# ztsh_autoguide.net
KiCad netlist of a schematic drawn in EAGLE
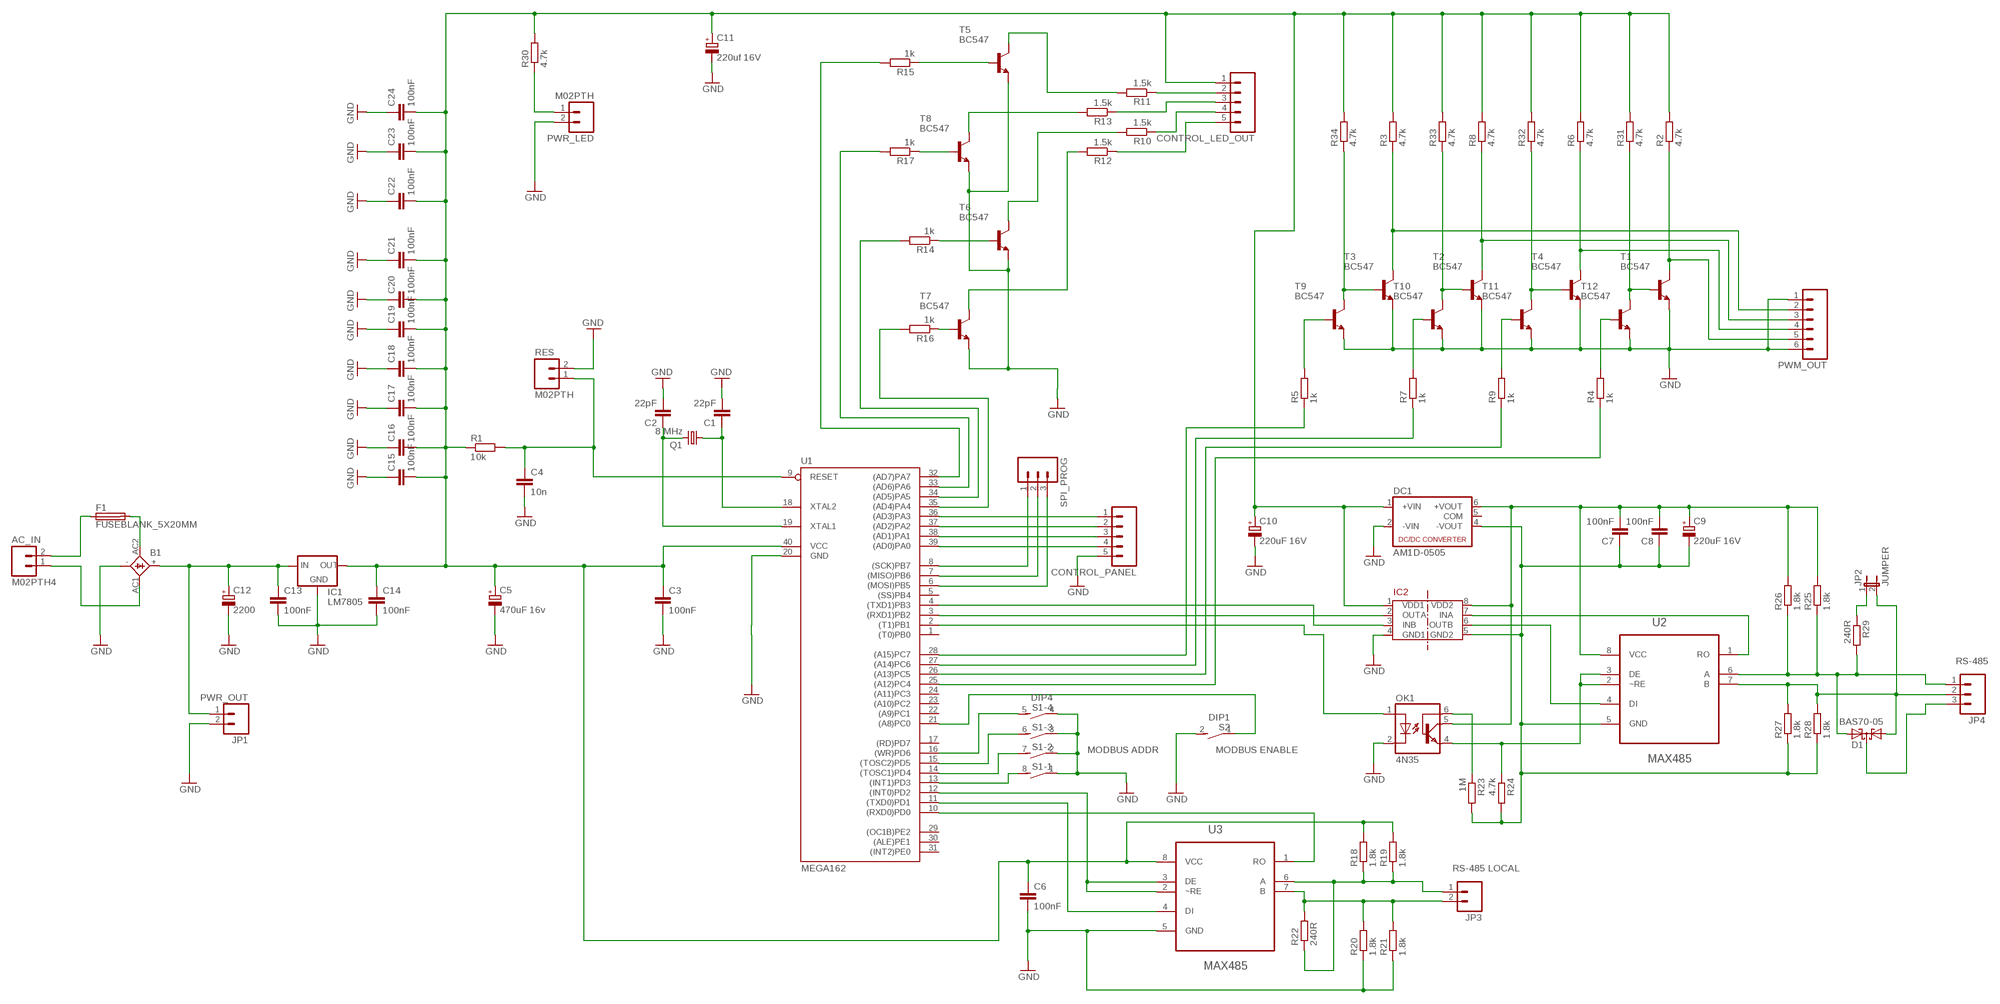
[diagram p0: schematic, sheet 1]

(export (version "E")
  (design (tool "Eeschema 10.0.6"))
  (components
    (comp (ref "AC_IN")
      (value "M02PTH4")
      (footprint "eagle-import:1X02_XTRA_BIG")
      (libsource (lib "eagle-import") (part "M02PTH4"))
    )
    (comp (ref "B1")
      (value "KBL")
      (footprint "eagle-import:KBL")
      (libsource (lib "eagle-import") (part "KBL"))
    )
    (comp (ref "C1")
      (value "22pF")
      (footprint "eagle-import:C025-024X044")
      (libsource (lib "eagle-import") (part "C-EU025-024X044"))
    )
    (comp (ref "C2")
      (value "22pF")
      (footprint "eagle-import:C025-024X044")
      (libsource (lib "eagle-import") (part "C-EU025-024X044"))
    )
    (comp (ref "C3")
      (value "100nF")
      (footprint "eagle-import:C0805")
      (libsource (lib "eagle-import") (part "C-EUC0805"))
    )
    (comp (ref "C4")
      (value "10n")
      (footprint "eagle-import:C0805")
      (libsource (lib "eagle-import") (part "C-EUC0805"))
    )
    (comp (ref "C5")
      (value "470uF 16v")
      (footprint "eagle-import:E2-5")
      (libsource (lib "eagle-import") (part "CPOL-EUE2-5"))
    )
    (comp (ref "C6")
      (value "100nF")
      (footprint "eagle-import:C0805")
      (libsource (lib "eagle-import") (part "C-EUC0805"))
    )
    (comp (ref "C7")
      (value "100nF")
      (footprint "eagle-import:C0805")
      (libsource (lib "eagle-import") (part "C-EUC0805"))
    )
    (comp (ref "C8")
      (value "100nF")
      (footprint "eagle-import:C0805")
      (libsource (lib "eagle-import") (part "C-EUC0805"))
    )
    (comp (ref "C9")
      (value "220uF 16V")
      (footprint "eagle-import:E2-5")
      (libsource (lib "eagle-import") (part "CPOL-EUE2-5"))
    )
    (comp (ref "C10")
      (value "220uF 16V")
      (footprint "eagle-import:E2-5")
      (libsource (lib "eagle-import") (part "CPOL-EUE2-5"))
    )
    (comp (ref "C11")
      (value "220uf 16V")
      (footprint "eagle-import:E2-5")
      (libsource (lib "eagle-import") (part "CPOL-EUE2-5"))
    )
    (comp (ref "C12")
      (value "2200")
      (footprint "eagle-import:E3,5-10")
      (libsource (lib "eagle-import") (part "resistor_CPOL-EUE3.5-10"))
    )
    (comp (ref "C13")
      (value "100nF")
      (footprint "eagle-import:C0805")
      (libsource (lib "eagle-import") (part "C-EUC0805"))
    )
    (comp (ref "C14")
      (value "100nF")
      (footprint "eagle-import:C0805")
      (libsource (lib "eagle-import") (part "C-EUC0805"))
    )
    (comp (ref "C15")
      (value "100nF")
      (footprint "eagle-import:C0805")
      (libsource (lib "eagle-import") (part "C-EUC0805"))
    )
    (comp (ref "C16")
      (value "100nF")
      (footprint "eagle-import:C0805")
      (libsource (lib "eagle-import") (part "C-EUC0805"))
    )
    (comp (ref "C17")
      (value "100nF")
      (footprint "eagle-import:C0805")
      (libsource (lib "eagle-import") (part "C-EUC0805"))
    )
    (comp (ref "C18")
      (value "100nF")
      (footprint "eagle-import:C0805")
      (libsource (lib "eagle-import") (part "C-EUC0805"))
    )
    (comp (ref "C19")
      (value "100nF")
      (footprint "eagle-import:C0805")
      (libsource (lib "eagle-import") (part "C-EUC0805"))
    )
    (comp (ref "C20")
      (value "100nF")
      (footprint "eagle-import:C0805")
      (libsource (lib "eagle-import") (part "C-EUC0805"))
    )
    (comp (ref "C21")
      (value "100nF")
      (footprint "eagle-import:C0805")
      (libsource (lib "eagle-import") (part "C-EUC0805"))
    )
    (comp (ref "C22")
      (value "100nF")
      (footprint "eagle-import:C0805")
      (libsource (lib "eagle-import") (part "C-EUC0805"))
    )
    (comp (ref "C23")
      (value "100nF")
      (footprint "eagle-import:C0805")
      (libsource (lib "eagle-import") (part "C-EUC0805"))
    )
    (comp (ref "C24")
      (value "100nF")
      (footprint "eagle-import:C0805")
      (libsource (lib "eagle-import") (part "C-EUC0805"))
    )
    (comp (ref "CONTROL_LED_OUT")
      (value "M05LOCK")
      (footprint "eagle-import:1X05_LOCK")
      (libsource (lib "eagle-import") (part "M05LOCK"))
    )
    (comp (ref "CONTROL_PANEL")
      (value "M05LOCK")
      (footprint "eagle-import:1X05_LOCK")
      (libsource (lib "eagle-import") (part "M05LOCK"))
    )
    (comp (ref "D1")
      (value "BAS70-05")
      (footprint "eagle-import:SOT23")
      (libsource (lib "eagle-import") (part "BAS70-05"))
    )
    (comp (ref "DC1")
      (value "AM1D-0505")
      (footprint "eagle-import:NMA")
      (fields (field (name "MF") "C & D TECHNOLOGIES, INC") (field (name "MPN") "NMA0515SC"))
      (libsource (lib "eagle-import") (part "NMA"))
    )
    (comp (ref "F1")
      (value "FUSEBLANK_5X20MM")
      (footprint "eagle-import:FUSE_HOLDER_5X20MM")
      (libsource (lib "eagle-import") (part "FUSEBLANK_5X20MM"))
    )
    (comp (ref "IC1")
      (value "LM7805")
      (footprint "eagle-import:TO-220-ALT")
      (libsource (lib "eagle-import") (part "V_REG_78XX-TO-220"))
    )
    (comp (ref "IC2")
      (value "ADUM1201")
      (footprint "eagle-import:SO8")
      (libsource (lib "eagle-import") (part "ADUM1201"))
    )
    (comp (ref "JP1")
      (value "PWR_OUT")
      (footprint "eagle-import:1X02_LOCK_LONGPADS")
      (libsource (lib "eagle-import") (part "M02LOCK_LONGPADS"))
    )
    (comp (ref "JP2")
      (value "JUMPER")
      (footprint "eagle-import:JP1")
      (libsource (lib "eagle-import") (part "JP1E"))
    )
    (comp (ref "JP3")
      (value "M02JST-PTH-VERT")
      (footprint "eagle-import:JST-2-PTH-VERT")
      (libsource (lib "eagle-import") (part "M02JST-PTH-VERT"))
    )
    (comp (ref "JP4")
      (value "M03JST-PTH-VERT")
      (footprint "eagle-import:JST-3-PTH-VERT")
      (libsource (lib "eagle-import") (part "M03JST-PTH-VERT"))
    )
    (comp (ref "OK1")
      (value "4N35")
      (footprint "eagle-import:DIL06")
      (fields (field (name "MF") "FAIRCHILD SEMICONDUCTOR"))
      (libsource (lib "eagle-import") (part "4N35"))
    )
    (comp (ref "PWM_OUT")
      (value "M06LOCK")
      (footprint "eagle-import:1X06_LOCK")
      (libsource (lib "eagle-import") (part "M06LOCK"))
    )
    (comp (ref "PWR_LED")
      (value "M02PTH")
      (footprint "eagle-import:1X02")
      (libsource (lib "eagle-import") (part "M02PTH"))
    )
    (comp (ref "Q1")
      (value "8 MHz")
      (footprint "eagle-import:HC18U-V")
      (libsource (lib "eagle-import") (part "CRYSTALHC18U-V"))
    )
    (comp (ref "R1")
      (value "10k")
      (footprint "eagle-import:0207_10")
      (libsource (lib "eagle-import") (part "R-EU_0207/10"))
    )
    (comp (ref "R2")
      (value "4.7k")
      (footprint "eagle-import:0204_7")
      (libsource (lib "eagle-import") (part "R-EU_0204/7"))
    )
    (comp (ref "R3")
      (value "4.7k")
      (footprint "eagle-import:0204_7")
      (libsource (lib "eagle-import") (part "R-EU_0204/7"))
    )
    (comp (ref "R4")
      (value "1k")
      (footprint "eagle-import:0204_7")
      (libsource (lib "eagle-import") (part "R-EU_0204/7"))
    )
    (comp (ref "R5")
      (value "1k")
      (footprint "eagle-import:0204_7")
      (libsource (lib "eagle-import") (part "R-EU_0204/7"))
    )
    (comp (ref "R6")
      (value "4.7k")
      (footprint "eagle-import:0204_7")
      (libsource (lib "eagle-import") (part "R-EU_0204/7"))
    )
    (comp (ref "R7")
      (value "1k")
      (footprint "eagle-import:0204_7")
      (libsource (lib "eagle-import") (part "R-EU_0204/7"))
    )
    (comp (ref "R8")
      (value "4.7k")
      (footprint "eagle-import:0204_7")
      (libsource (lib "eagle-import") (part "R-EU_0204/7"))
    )
    (comp (ref "R9")
      (value "1k")
      (footprint "eagle-import:0204_7")
      (libsource (lib "eagle-import") (part "R-EU_0204/7"))
    )
    (comp (ref "R10")
      (value "1.5k")
      (footprint "eagle-import:0204_7")
      (libsource (lib "eagle-import") (part "R-EU_0204/7"))
    )
    (comp (ref "R11")
      (value "1.5k")
      (footprint "eagle-import:0204_7")
      (libsource (lib "eagle-import") (part "R-EU_0204/7"))
    )
    (comp (ref "R12")
      (value "1.5k")
      (footprint "eagle-import:0204_7")
      (libsource (lib "eagle-import") (part "R-EU_0204/7"))
    )
    (comp (ref "R13")
      (value "1.5k")
      (footprint "eagle-import:0204_7")
      (libsource (lib "eagle-import") (part "R-EU_0204/7"))
    )
    (comp (ref "R14")
      (value "1k")
      (footprint "eagle-import:0204_7")
      (libsource (lib "eagle-import") (part "R-EU_0204/7"))
    )
    (comp (ref "R15")
      (value "1k")
      (footprint "eagle-import:0204_7")
      (libsource (lib "eagle-import") (part "R-EU_0204/7"))
    )
    (comp (ref "R16")
      (value "1k")
      (footprint "eagle-import:0204_7")
      (libsource (lib "eagle-import") (part "R-EU_0204/7"))
    )
    (comp (ref "R17")
      (value "1k")
      (footprint "eagle-import:0204_7")
      (libsource (lib "eagle-import") (part "R-EU_0204/7"))
    )
    (comp (ref "R18")
      (value "1.8k")
      (footprint "eagle-import:R0805")
      (libsource (lib "eagle-import") (part "R-EU_R0805"))
    )
    (comp (ref "R19")
      (value "1.8k")
      (footprint "eagle-import:R0805")
      (libsource (lib "eagle-import") (part "R-EU_R0805"))
    )
    (comp (ref "R20")
      (value "1.8k")
      (footprint "eagle-import:R0805")
      (libsource (lib "eagle-import") (part "R-EU_R0805"))
    )
    (comp (ref "R21")
      (value "1.8k")
      (footprint "eagle-import:R0805")
      (libsource (lib "eagle-import") (part "R-EU_R0805"))
    )
    (comp (ref "R22")
      (value "240R")
      (footprint "eagle-import:R0805")
      (libsource (lib "eagle-import") (part "R-EU_R0805"))
    )
    (comp (ref "R23")
      (value "1M")
      (footprint "eagle-import:0204_7")
      (libsource (lib "eagle-import") (part "R-EU_0204/7"))
    )
    (comp (ref "R24")
      (value "4.7k")
      (footprint "eagle-import:0204_7")
      (libsource (lib "eagle-import") (part "R-EU_0204/7"))
    )
    (comp (ref "R25")
      (value "1.8k")
      (footprint "eagle-import:R0805")
      (libsource (lib "eagle-import") (part "R-EU_R0805"))
    )
    (comp (ref "R26")
      (value "1.8k")
      (footprint "eagle-import:R0805")
      (libsource (lib "eagle-import") (part "R-EU_R0805"))
    )
    (comp (ref "R27")
      (value "1.8k")
      (footprint "eagle-import:R0805")
      (libsource (lib "eagle-import") (part "R-EU_R0805"))
    )
    (comp (ref "R28")
      (value "1.8k")
      (footprint "eagle-import:R0805")
      (libsource (lib "eagle-import") (part "R-EU_R0805"))
    )
    (comp (ref "R29")
      (value "240R")
      (footprint "eagle-import:R0805")
      (libsource (lib "eagle-import") (part "R-EU_R0805"))
    )
    (comp (ref "R30")
      (value "4.7k")
      (footprint "eagle-import:0207_10")
      (libsource (lib "eagle-import") (part "R-EU_0207/10"))
    )
    (comp (ref "R31")
      (value "4.7k")
      (footprint "eagle-import:0204_7")
      (libsource (lib "eagle-import") (part "R-EU_0204/7"))
    )
    (comp (ref "R32")
      (value "4.7k")
      (footprint "eagle-import:0204_7")
      (libsource (lib "eagle-import") (part "R-EU_0204/7"))
    )
    (comp (ref "R33")
      (value "4.7k")
      (footprint "eagle-import:0204_7")
      (libsource (lib "eagle-import") (part "R-EU_0204/7"))
    )
    (comp (ref "R34")
      (value "4.7k")
      (footprint "eagle-import:0204_7")
      (libsource (lib "eagle-import") (part "R-EU_0204/7"))
    )
    (comp (ref "RES")
      (value "M02PTH")
      (footprint "eagle-import:1X02")
      (libsource (lib "eagle-import") (part "M02PTH"))
    )
    (comp (ref "S1")
      (value "DIP4")
      (footprint "eagle-import:DIP04S")
      (libsource (lib "eagle-import") (part "DIP04S"))
    )
    (comp (ref "S2")
      (value "DIP1")
      (footprint "eagle-import:DS-01")
      (libsource (lib "eagle-import") (part "DS01E"))
    )
    (comp (ref "SPI_PROG")
      (value "M03LOCK")
      (footprint "eagle-import:1X03_LOCK")
      (libsource (lib "eagle-import") (part "M03LOCK"))
    )
    (comp (ref "T1")
      (value "BC547")
      (footprint "eagle-import:TO92")
      (libsource (lib "eagle-import") (part "BC547"))
    )
    (comp (ref "T2")
      (value "BC547")
      (footprint "eagle-import:TO92")
      (libsource (lib "eagle-import") (part "BC547"))
    )
    (comp (ref "T3")
      (value "BC547")
      (footprint "eagle-import:TO92")
      (libsource (lib "eagle-import") (part "BC547"))
    )
    (comp (ref "T4")
      (value "BC547")
      (footprint "eagle-import:TO92")
      (libsource (lib "eagle-import") (part "BC547"))
    )
    (comp (ref "T5")
      (value "BC547")
      (footprint "eagle-import:TO92")
      (libsource (lib "eagle-import") (part "BC547"))
    )
    (comp (ref "T6")
      (value "BC547")
      (footprint "eagle-import:TO92")
      (libsource (lib "eagle-import") (part "BC547"))
    )
    (comp (ref "T7")
      (value "BC547")
      (footprint "eagle-import:TO92")
      (libsource (lib "eagle-import") (part "BC547"))
    )
    (comp (ref "T8")
      (value "BC547")
      (footprint "eagle-import:TO92")
      (libsource (lib "eagle-import") (part "BC547"))
    )
    (comp (ref "T9")
      (value "BC547")
      (footprint "eagle-import:TO92")
      (libsource (lib "eagle-import") (part "BC547"))
    )
    (comp (ref "T10")
      (value "BC547")
      (footprint "eagle-import:TO92")
      (libsource (lib "eagle-import") (part "BC547"))
    )
    (comp (ref "T11")
      (value "BC547")
      (footprint "eagle-import:TO92")
      (libsource (lib "eagle-import") (part "BC547"))
    )
    (comp (ref "T12")
      (value "BC547")
      (footprint "eagle-import:TO92")
      (libsource (lib "eagle-import") (part "BC547"))
    )
    (comp (ref "U1")
      (value "MEGA162")
      (footprint "eagle-import:DIL40")
      (libsource (lib "eagle-import") (part "MEGA162PV-P"))
    )
    (comp (ref "U2")
      (value "MAX485")
      (footprint "eagle-import:SOIC127P600X175-8N")
      (fields (field (name "MPN") "MAX485CSA+"))
      (libsource (lib "eagle-import") (part "MAX485CSA+"))
    )
    (comp (ref "U3")
      (value "MAX485")
      (footprint "eagle-import:SOIC127P600X175-8N")
      (fields (field (name "MPN") "MAX485CSA+"))
      (libsource (lib "eagle-import") (part "MAX485CSA+"))
    )
  )
  (nets
    (net (code "1") (name "GND") (class "Default")
      (node (ref "B1") (pin "-") (pinfunction "-_-") (pintype "passive"))
      (node (ref "C1") (pin "2") (pinfunction "2_2") (pintype "passive"))
      (node (ref "C10") (pin "-") (pinfunction "-_-") (pintype "passive"))
      (node (ref "C11") (pin "-") (pinfunction "-_-") (pintype "passive"))
      (node (ref "C12") (pin "-") (pinfunction "-_-") (pintype "passive"))
      (node (ref "C13") (pin "2") (pinfunction "2_2") (pintype "passive"))
      (node (ref "C14") (pin "2") (pinfunction "2_2") (pintype "passive"))
      (node (ref "C15") (pin "1") (pinfunction "1_1") (pintype "passive"))
      (node (ref "C16") (pin "1") (pinfunction "1_1") (pintype "passive"))
      (node (ref "C17") (pin "1") (pinfunction "1_1") (pintype "passive"))
      (node (ref "C18") (pin "1") (pinfunction "1_1") (pintype "passive"))
      (node (ref "C19") (pin "1") (pinfunction "1_1") (pintype "passive"))
      (node (ref "C2") (pin "2") (pinfunction "2_2") (pintype "passive"))
      (node (ref "C20") (pin "1") (pinfunction "1_1") (pintype "passive"))
      (node (ref "C21") (pin "1") (pinfunction "1_1") (pintype "passive"))
      (node (ref "C22") (pin "1") (pinfunction "1_1") (pintype "passive"))
      (node (ref "C23") (pin "1") (pinfunction "1_1") (pintype "passive"))
      (node (ref "C24") (pin "1") (pinfunction "1_1") (pintype "passive"))
      (node (ref "C3") (pin "2") (pinfunction "2_2") (pintype "passive"))
      (node (ref "C4") (pin "2") (pinfunction "2_2") (pintype "passive"))
      (node (ref "C5") (pin "-") (pinfunction "-_-") (pintype "passive"))
      (node (ref "C6") (pin "2") (pinfunction "2_2") (pintype "passive"))
      (node (ref "CONTROL_PANEL") (pin "5") (pinfunction "5_5") (pintype "passive"))
      (node (ref "DC1") (pin "2") (pinfunction "-VIN_2") (pintype "passive"))
      (node (ref "IC1") (pin "GND") (pinfunction "GND_GND") (pintype "input"))
      (node (ref "IC2") (pin "4") (pinfunction "GND1_4") (pintype "power_in"))
      (node (ref "JP1") (pin "2") (pinfunction "2_2") (pintype "passive"))
      (node (ref "OK1") (pin "2") (pinfunction "C_2") (pintype "passive"))
      (node (ref "PWM_OUT") (pin "1") (pinfunction "1_1") (pintype "passive"))
      (node (ref "PWM_OUT") (pin "6") (pinfunction "6_6") (pintype "passive"))
      (node (ref "PWR_LED") (pin "2") (pinfunction "2_2") (pintype "passive"))
      (node (ref "R20") (pin "1") (pinfunction "1_1") (pintype "passive"))
      (node (ref "R21") (pin "1") (pinfunction "1_1") (pintype "passive"))
      (node (ref "RES") (pin "2") (pinfunction "2_2") (pintype "passive"))
      (node (ref "S1") (pin "1") (pinfunction "1_1") (pintype "passive"))
      (node (ref "S1") (pin "2") (pinfunction "1_2") (pintype "passive"))
      (node (ref "S1") (pin "3") (pinfunction "1_3") (pintype "passive"))
      (node (ref "S1") (pin "4") (pinfunction "1_4") (pintype "passive"))
      (node (ref "S2") (pin "2") (pinfunction "2_2") (pintype "passive"))
      (node (ref "T1") (pin "1") (pinfunction "E_1") (pintype "passive"))
      (node (ref "T10") (pin "1") (pinfunction "E_1") (pintype "passive"))
      (node (ref "T11") (pin "1") (pinfunction "E_1") (pintype "passive"))
      (node (ref "T12") (pin "1") (pinfunction "E_1") (pintype "passive"))
      (node (ref "T2") (pin "1") (pinfunction "E_1") (pintype "passive"))
      (node (ref "T3") (pin "1") (pinfunction "E_1") (pintype "passive"))
      (node (ref "T4") (pin "1") (pinfunction "E_1") (pintype "passive"))
      (node (ref "T5") (pin "1") (pinfunction "E_1") (pintype "passive"))
      (node (ref "T6") (pin "1") (pinfunction "E_1") (pintype "passive"))
      (node (ref "T7") (pin "1") (pinfunction "E_1") (pintype "passive"))
      (node (ref "T8") (pin "1") (pinfunction "E_1") (pintype "passive"))
      (node (ref "T9") (pin "1") (pinfunction "E_1") (pintype "passive"))
      (node (ref "U1") (pin "20") (pinfunction "GND_20") (pintype "power_in"))
      (node (ref "U3") (pin "5") (pinfunction "GND_5") (pintype "passive"))
    )
    (net (code "2") (name "Net-(AC_IN-Pad2)") (class "Default")
      (node (ref "AC_IN") (pin "2") (pinfunction "2_2") (pintype "passive"))
      (node (ref "F1") (pin "1") (pinfunction "1_1") (pintype "passive"))
    )
    (net (code "3") (name "Net-(B1-AC1)") (class "Default")
      (node (ref "B1") (pin "AC2") (pinfunction "AC1_AC2") (pintype "passive"))
      (node (ref "F1") (pin "2") (pinfunction "2_2") (pintype "passive"))
    )
    (net (code "4") (name "Net-(B1-AC2)") (class "Default")
      (node (ref "AC_IN") (pin "1") (pinfunction "1_1") (pintype "passive"))
      (node (ref "B1") (pin "AC1") (pinfunction "AC2_AC1") (pintype "passive"))
    )
    (net (code "5") (name "Net-(B1-Pad+)") (class "Default")
      (node (ref "B1") (pin "+") (pinfunction "+_+") (pintype "passive"))
      (node (ref "C12") (pin "+") (pinfunction "+_+") (pintype "passive"))
      (node (ref "C13") (pin "1") (pinfunction "1_1") (pintype "passive"))
      (node (ref "IC1") (pin "IN") (pinfunction "IN_IN") (pintype "input"))
      (node (ref "JP1") (pin "1") (pinfunction "1_1") (pintype "passive"))
    )
    (net (code "6") (name "Net-(CONTROL_LED_OUT-Pad2)") (class "Default")
      (node (ref "CONTROL_LED_OUT") (pin "2") (pinfunction "2_2") (pintype "passive"))
      (node (ref "R11") (pin "1") (pinfunction "1_1") (pintype "passive"))
    )
    (net (code "7") (name "Net-(CONTROL_LED_OUT-Pad3)") (class "Default")
      (node (ref "CONTROL_LED_OUT") (pin "3") (pinfunction "3_3") (pintype "passive"))
      (node (ref "R13") (pin "1") (pinfunction "1_1") (pintype "passive"))
    )
    (net (code "8") (name "Net-(CONTROL_LED_OUT-Pad4)") (class "Default")
      (node (ref "CONTROL_LED_OUT") (pin "4") (pinfunction "4_4") (pintype "passive"))
      (node (ref "R10") (pin "1") (pinfunction "1_1") (pintype "passive"))
    )
    (net (code "9") (name "Net-(CONTROL_LED_OUT-Pad5)") (class "Default")
      (node (ref "CONTROL_LED_OUT") (pin "5") (pinfunction "5_5") (pintype "passive"))
      (node (ref "R12") (pin "1") (pinfunction "1_1") (pintype "passive"))
    )
    (net (code "10") (name "Net-(D1-A1)") (class "Default")
      (node (ref "D1") (pin "1") (pinfunction "A1_1") (pintype "passive"))
      (node (ref "JP2") (pin "2") (pinfunction "2_2") (pintype "passive"))
      (node (ref "JP4") (pin "2") (pinfunction "2_2") (pintype "passive"))
      (node (ref "R27") (pin "2") (pinfunction "2_2") (pintype "passive"))
      (node (ref "R28") (pin "2") (pinfunction "2_2") (pintype "passive"))
      (node (ref "U2") (pin "7") (pinfunction "B_7") (pintype "bidirectional"))
    )
    (net (code "11") (name "Net-(D1-A2)") (class "Default")
      (node (ref "D1") (pin "2") (pinfunction "A2_2") (pintype "passive"))
      (node (ref "JP4") (pin "1") (pinfunction "1_1") (pintype "passive"))
      (node (ref "R25") (pin "1") (pinfunction "1_1") (pintype "passive"))
      (node (ref "R26") (pin "1") (pinfunction "1_1") (pintype "passive"))
      (node (ref "R29") (pin "2") (pinfunction "2_2") (pintype "passive"))
      (node (ref "U2") (pin "6") (pinfunction "A_6") (pintype "bidirectional"))
    )
    (net (code "12") (name "Net-(D1-C)") (class "Default")
      (node (ref "D1") (pin "3") (pinfunction "C_3") (pintype "passive"))
      (node (ref "JP4") (pin "3") (pinfunction "3_3") (pintype "passive"))
    )
    (net (code "13") (name "Net-(DC1-+VIN)") (class "Default")
      (node (ref "C10") (pin "+") (pinfunction "+_+") (pintype "passive"))
      (node (ref "C11") (pin "+") (pinfunction "+_+") (pintype "passive"))
      (node (ref "C14") (pin "1") (pinfunction "1_1") (pintype "passive"))
      (node (ref "C15") (pin "2") (pinfunction "2_2") (pintype "passive"))
      (node (ref "C16") (pin "2") (pinfunction "2_2") (pintype "passive"))
      (node (ref "C17") (pin "2") (pinfunction "2_2") (pintype "passive"))
      (node (ref "C18") (pin "2") (pinfunction "2_2") (pintype "passive"))
      (node (ref "C19") (pin "2") (pinfunction "2_2") (pintype "passive"))
      (node (ref "C20") (pin "2") (pinfunction "2_2") (pintype "passive"))
      (node (ref "C21") (pin "2") (pinfunction "2_2") (pintype "passive"))
      (node (ref "C22") (pin "2") (pinfunction "2_2") (pintype "passive"))
      (node (ref "C23") (pin "2") (pinfunction "2_2") (pintype "passive"))
      (node (ref "C24") (pin "2") (pinfunction "2_2") (pintype "passive"))
      (node (ref "C3") (pin "1") (pinfunction "1_1") (pintype "passive"))
      (node (ref "C5") (pin "+") (pinfunction "+_+") (pintype "passive"))
      (node (ref "C6") (pin "1") (pinfunction "1_1") (pintype "passive"))
      (node (ref "CONTROL_LED_OUT") (pin "1") (pinfunction "1_1") (pintype "passive"))
      (node (ref "DC1") (pin "1") (pinfunction "+VIN_1") (pintype "passive"))
      (node (ref "IC1") (pin "OUT") (pinfunction "OUT_OUT") (pintype "output"))
      (node (ref "IC2") (pin "1") (pinfunction "VDD1_1") (pintype "power_in"))
      (node (ref "R1") (pin "1") (pinfunction "1_1") (pintype "passive"))
      (node (ref "R18") (pin "2") (pinfunction "2_2") (pintype "passive"))
      (node (ref "R19") (pin "2") (pinfunction "2_2") (pintype "passive"))
      (node (ref "R2") (pin "2") (pinfunction "2_2") (pintype "passive"))
      (node (ref "R3") (pin "2") (pinfunction "2_2") (pintype "passive"))
      (node (ref "R30") (pin "2") (pinfunction "2_2") (pintype "passive"))
      (node (ref "R31") (pin "2") (pinfunction "2_2") (pintype "passive"))
      (node (ref "R32") (pin "2") (pinfunction "2_2") (pintype "passive"))
      (node (ref "R33") (pin "2") (pinfunction "2_2") (pintype "passive"))
      (node (ref "R34") (pin "2") (pinfunction "2_2") (pintype "passive"))
      (node (ref "R6") (pin "2") (pinfunction "2_2") (pintype "passive"))
      (node (ref "R8") (pin "2") (pinfunction "2_2") (pintype "passive"))
      (node (ref "U1") (pin "40") (pinfunction "VCC_40") (pintype "power_in"))
      (node (ref "U3") (pin "8") (pinfunction "VCC_8") (pintype "power_in"))
    )
    (net (code "14") (name "Net-(DC1-+VOUT)") (class "Default")
      (node (ref "C7") (pin "2") (pinfunction "2_2") (pintype "passive"))
      (node (ref "C8") (pin "2") (pinfunction "2_2") (pintype "passive"))
      (node (ref "C9") (pin "+") (pinfunction "+_+") (pintype "passive"))
      (node (ref "DC1") (pin "6") (pinfunction "+VOUT_6") (pintype "passive"))
      (node (ref "IC2") (pin "8") (pinfunction "VDD2_8") (pintype "power_in"))
      (node (ref "OK1") (pin "5") (pinfunction "COL_5") (pintype "passive"))
      (node (ref "R25") (pin "2") (pinfunction "2_2") (pintype "passive"))
      (node (ref "R26") (pin "2") (pinfunction "2_2") (pintype "passive"))
      (node (ref "U2") (pin "8") (pinfunction "VCC_8") (pintype "power_in"))
    )
    (net (code "15") (name "Net-(DC1--VOUT)") (class "Default")
      (node (ref "C7") (pin "1") (pinfunction "1_1") (pintype "passive"))
      (node (ref "C8") (pin "1") (pinfunction "1_1") (pintype "passive"))
      (node (ref "C9") (pin "-") (pinfunction "-_-") (pintype "passive"))
      (node (ref "DC1") (pin "4") (pinfunction "-VOUT_4") (pintype "passive"))
      (node (ref "IC2") (pin "5") (pinfunction "GND2_5") (pintype "power_in"))
      (node (ref "R23") (pin "2") (pinfunction "2_2") (pintype "passive"))
      (node (ref "R24") (pin "2") (pinfunction "2_2") (pintype "passive"))
      (node (ref "R27") (pin "1") (pinfunction "1_1") (pintype "passive"))
      (node (ref "R28") (pin "1") (pinfunction "1_1") (pintype "passive"))
      (node (ref "U2") (pin "5") (pinfunction "GND_5") (pintype "passive"))
    )
    (net (code "16") (name "Net-(IC2-INA)") (class "Default")
      (node (ref "IC2") (pin "7") (pinfunction "INA_7") (pintype "input"))
      (node (ref "U2") (pin "1") (pinfunction "RO_1") (pintype "output"))
    )
    (net (code "17") (name "Net-(IC2-INB)") (class "Default")
      (node (ref "IC2") (pin "3") (pinfunction "INB_3") (pintype "input"))
      (node (ref "U1") (pin "4") (pinfunction "(TXD1)PB3_4") (pintype "bidirectional"))
    )
    (net (code "18") (name "Net-(IC2-OUTA)") (class "Default")
      (node (ref "IC2") (pin "2") (pinfunction "OUTA_2") (pintype "output"))
      (node (ref "U1") (pin "3") (pinfunction "(RXD1)PB2_3") (pintype "bidirectional"))
    )
    (net (code "19") (name "Net-(IC2-OUTB)") (class "Default")
      (node (ref "IC2") (pin "6") (pinfunction "OUTB_6") (pintype "output"))
      (node (ref "U2") (pin "4") (pinfunction "DI_4") (pintype "input"))
    )
    (net (code "20") (name "Net-(JP2-Pad1)") (class "Default")
      (node (ref "JP2") (pin "1") (pinfunction "1_1") (pintype "passive"))
      (node (ref "R29") (pin "1") (pinfunction "1_1") (pintype "passive"))
    )
    (net (code "21") (name "Net-(OK1-A)") (class "Default")
      (node (ref "OK1") (pin "1") (pinfunction "A_1") (pintype "passive"))
      (node (ref "U1") (pin "2") (pinfunction "(T1)PB1_2") (pintype "bidirectional"))
    )
    (net (code "22") (name "Net-(OK1-BAS)") (class "Default")
      (node (ref "OK1") (pin "6") (pinfunction "BAS_6") (pintype "passive"))
      (node (ref "R23") (pin "1") (pinfunction "1_1") (pintype "passive"))
    )
    (net (code "23") (name "Net-(OK1-EMI)") (class "Default")
      (node (ref "OK1") (pin "4") (pinfunction "EMI_4") (pintype "passive"))
      (node (ref "R24") (pin "1") (pinfunction "1_1") (pintype "passive"))
      (node (ref "U2") (pin "2") (pinfunction "~{RE}_2") (pintype "input"))
      (node (ref "U2") (pin "3") (pinfunction "DE_3") (pintype "input"))
    )
    (net (code "24") (name "Net-(PWR_LED-Pad1)") (class "Default")
      (node (ref "PWR_LED") (pin "1") (pinfunction "1_1") (pintype "passive"))
      (node (ref "R30") (pin "1") (pinfunction "1_1") (pintype "passive"))
    )
    (net (code "25") (name "Net-(S1A-2)") (class "Default")
      (node (ref "S1") (pin "8") (pinfunction "2_8") (pintype "passive"))
      (node (ref "U1") (pin "13") (pinfunction "(INT1)PD3_13") (pintype "bidirectional"))
    )
    (net (code "26") (name "Net-(S1B-2)") (class "Default")
      (node (ref "S1") (pin "7") (pinfunction "2_7") (pintype "passive"))
      (node (ref "U1") (pin "14") (pinfunction "(TOSC1)PD4_14") (pintype "bidirectional"))
    )
    (net (code "27") (name "Net-(S1C-2)") (class "Default")
      (node (ref "S1") (pin "6") (pinfunction "2_6") (pintype "passive"))
      (node (ref "U1") (pin "15") (pinfunction "(TOSC2)PD5_15") (pintype "bidirectional"))
    )
    (net (code "28") (name "Net-(S1D-2)") (class "Default")
      (node (ref "S1") (pin "5") (pinfunction "2_5") (pintype "passive"))
      (node (ref "U1") (pin "16") (pinfunction "(WR)PD6_16") (pintype "bidirectional"))
    )
    (net (code "29") (name "Net-(T1-B)") (class "Default")
      (node (ref "R31") (pin "1") (pinfunction "1_1") (pintype "passive"))
      (node (ref "T1") (pin "2") (pinfunction "B_2") (pintype "passive"))
      (node (ref "T12") (pin "3") (pinfunction "C_3") (pintype "passive"))
    )
    (net (code "30") (name "Net-(T1-C)") (class "Default")
      (node (ref "PWM_OUT") (pin "5") (pinfunction "5_5") (pintype "passive"))
      (node (ref "R2") (pin "1") (pinfunction "1_1") (pintype "passive"))
      (node (ref "T1") (pin "3") (pinfunction "C_3") (pintype "passive"))
    )
    (net (code "31") (name "Net-(T2-C)") (class "Default")
      (node (ref "PWM_OUT") (pin "3") (pinfunction "3_3") (pintype "passive"))
      (node (ref "R8") (pin "1") (pinfunction "1_1") (pintype "passive"))
      (node (ref "T2") (pin "3") (pinfunction "C_3") (pintype "passive"))
    )
    (net (code "32") (name "Net-(T3-B)") (class "Default")
      (node (ref "R34") (pin "1") (pinfunction "1_1") (pintype "passive"))
      (node (ref "T3") (pin "2") (pinfunction "B_2") (pintype "passive"))
      (node (ref "T9") (pin "3") (pinfunction "C_3") (pintype "passive"))
    )
    (net (code "33") (name "Net-(T3-C)") (class "Default")
      (node (ref "PWM_OUT") (pin "2") (pinfunction "2_2") (pintype "passive"))
      (node (ref "R3") (pin "1") (pinfunction "1_1") (pintype "passive"))
      (node (ref "T3") (pin "3") (pinfunction "C_3") (pintype "passive"))
    )
    (net (code "34") (name "Net-(T4-C)") (class "Default")
      (node (ref "PWM_OUT") (pin "4") (pinfunction "4_4") (pintype "passive"))
      (node (ref "R6") (pin "1") (pinfunction "1_1") (pintype "passive"))
      (node (ref "T4") (pin "3") (pinfunction "C_3") (pintype "passive"))
    )
    (net (code "35") (name "Net-(T5-B)") (class "Default")
      (node (ref "R15") (pin "1") (pinfunction "1_1") (pintype "passive"))
      (node (ref "T5") (pin "2") (pinfunction "B_2") (pintype "passive"))
    )
    (net (code "36") (name "Net-(T5-C)") (class "Default")
      (node (ref "R11") (pin "2") (pinfunction "2_2") (pintype "passive"))
      (node (ref "T5") (pin "3") (pinfunction "C_3") (pintype "passive"))
    )
    (net (code "37") (name "Net-(T6-B)") (class "Default")
      (node (ref "R14") (pin "1") (pinfunction "1_1") (pintype "passive"))
      (node (ref "T6") (pin "2") (pinfunction "B_2") (pintype "passive"))
    )
    (net (code "38") (name "Net-(T6-C)") (class "Default")
      (node (ref "R10") (pin "2") (pinfunction "2_2") (pintype "passive"))
      (node (ref "T6") (pin "3") (pinfunction "C_3") (pintype "passive"))
    )
    (net (code "39") (name "Net-(T7-B)") (class "Default")
      (node (ref "R16") (pin "1") (pinfunction "1_1") (pintype "passive"))
      (node (ref "T7") (pin "2") (pinfunction "B_2") (pintype "passive"))
    )
    (net (code "40") (name "Net-(T7-C)") (class "Default")
      (node (ref "R12") (pin "2") (pinfunction "2_2") (pintype "passive"))
      (node (ref "T7") (pin "3") (pinfunction "C_3") (pintype "passive"))
    )
    (net (code "41") (name "Net-(T8-B)") (class "Default")
      (node (ref "R17") (pin "1") (pinfunction "1_1") (pintype "passive"))
      (node (ref "T8") (pin "2") (pinfunction "B_2") (pintype "passive"))
    )
    (net (code "42") (name "Net-(T8-C)") (class "Default")
      (node (ref "R13") (pin "2") (pinfunction "2_2") (pintype "passive"))
      (node (ref "T8") (pin "3") (pinfunction "C_3") (pintype "passive"))
    )
    (net (code "43") (name "Net-(T9-B)") (class "Default")
      (node (ref "R5") (pin "2") (pinfunction "2_2") (pintype "passive"))
      (node (ref "T9") (pin "2") (pinfunction "B_2") (pintype "passive"))
    )
    (net (code "44") (name "Net-(T10-B)") (class "Default")
      (node (ref "R7") (pin "2") (pinfunction "2_2") (pintype "passive"))
      (node (ref "T10") (pin "2") (pinfunction "B_2") (pintype "passive"))
    )
    (net (code "45") (name "Net-(T10-C)") (class "Default")
      (node (ref "R33") (pin "1") (pinfunction "1_1") (pintype "passive"))
      (node (ref "T10") (pin "3") (pinfunction "C_3") (pintype "passive"))
      (node (ref "T2") (pin "2") (pinfunction "B_2") (pintype "passive"))
    )
    (net (code "46") (name "Net-(T11-B)") (class "Default")
      (node (ref "R9") (pin "2") (pinfunction "2_2") (pintype "passive"))
      (node (ref "T11") (pin "2") (pinfunction "B_2") (pintype "passive"))
    )
    (net (code "47") (name "Net-(T11-C)") (class "Default")
      (node (ref "R32") (pin "1") (pinfunction "1_1") (pintype "passive"))
      (node (ref "T11") (pin "3") (pinfunction "C_3") (pintype "passive"))
      (node (ref "T4") (pin "2") (pinfunction "B_2") (pintype "passive"))
    )
    (net (code "48") (name "Net-(T12-B)") (class "Default")
      (node (ref "R4") (pin "2") (pinfunction "2_2") (pintype "passive"))
      (node (ref "T12") (pin "2") (pinfunction "B_2") (pintype "passive"))
    )
    (net (code "49") (name "Net-(U1-(A8)PC0)") (class "Default")
      (node (ref "S2") (pin "1") (pinfunction "1_1") (pintype "passive"))
      (node (ref "U1") (pin "21") (pinfunction "(A8)PC0_21") (pintype "bidirectional"))
    )
    (net (code "50") (name "Net-(U1-(A12)PC4)") (class "Default")
      (node (ref "R4") (pin "1") (pinfunction "1_1") (pintype "passive"))
      (node (ref "U1") (pin "25") (pinfunction "(A12)PC4_25") (pintype "bidirectional"))
    )
    (net (code "51") (name "Net-(U1-(A13)PC5)") (class "Default")
      (node (ref "R9") (pin "1") (pinfunction "1_1") (pintype "passive"))
      (node (ref "U1") (pin "26") (pinfunction "(A13)PC5_26") (pintype "bidirectional"))
    )
    (net (code "52") (name "Net-(U1-(A14)PC6)") (class "Default")
      (node (ref "R7") (pin "1") (pinfunction "1_1") (pintype "passive"))
      (node (ref "U1") (pin "27") (pinfunction "(A14)PC6_27") (pintype "bidirectional"))
    )
    (net (code "53") (name "Net-(U1-(A15)PC7)") (class "Default")
      (node (ref "R5") (pin "1") (pinfunction "1_1") (pintype "passive"))
      (node (ref "U1") (pin "28") (pinfunction "(A15)PC7_28") (pintype "bidirectional"))
    )
    (net (code "54") (name "Net-(U1-(AD0)PA0)") (class "Default")
      (node (ref "CONTROL_PANEL") (pin "4") (pinfunction "4_4") (pintype "passive"))
      (node (ref "U1") (pin "39") (pinfunction "(AD0)PA0_39") (pintype "bidirectional"))
    )
    (net (code "55") (name "Net-(U1-(AD1)PA1)") (class "Default")
      (node (ref "CONTROL_PANEL") (pin "3") (pinfunction "3_3") (pintype "passive"))
      (node (ref "U1") (pin "38") (pinfunction "(AD1)PA1_38") (pintype "bidirectional"))
    )
    (net (code "56") (name "Net-(U1-(AD2)PA2)") (class "Default")
      (node (ref "CONTROL_PANEL") (pin "2") (pinfunction "2_2") (pintype "passive"))
      (node (ref "U1") (pin "37") (pinfunction "(AD2)PA2_37") (pintype "bidirectional"))
    )
    (net (code "57") (name "Net-(U1-(AD3)PA3)") (class "Default")
      (node (ref "CONTROL_PANEL") (pin "1") (pinfunction "1_1") (pintype "passive"))
      (node (ref "U1") (pin "36") (pinfunction "(AD3)PA3_36") (pintype "bidirectional"))
    )
    (net (code "58") (name "Net-(U1-(AD4)PA4)") (class "Default")
      (node (ref "R16") (pin "2") (pinfunction "2_2") (pintype "passive"))
      (node (ref "U1") (pin "35") (pinfunction "(AD4)PA4_35") (pintype "bidirectional"))
    )
    (net (code "59") (name "Net-(U1-(AD5)PA5)") (class "Default")
      (node (ref "R14") (pin "2") (pinfunction "2_2") (pintype "passive"))
      (node (ref "U1") (pin "34") (pinfunction "(AD5)PA5_34") (pintype "bidirectional"))
    )
    (net (code "60") (name "Net-(U1-(AD6)PA6)") (class "Default")
      (node (ref "R17") (pin "2") (pinfunction "2_2") (pintype "passive"))
      (node (ref "U1") (pin "33") (pinfunction "(AD6)PA6_33") (pintype "bidirectional"))
    )
    (net (code "61") (name "Net-(U1-(AD7)PA7)") (class "Default")
      (node (ref "R15") (pin "2") (pinfunction "2_2") (pintype "passive"))
      (node (ref "U1") (pin "32") (pinfunction "(AD7)PA7_32") (pintype "bidirectional"))
    )
    (net (code "62") (name "Net-(U1-(INT0)PD2)") (class "Default")
      (node (ref "U1") (pin "12") (pinfunction "(INT0)PD2_12") (pintype "bidirectional"))
      (node (ref "U3") (pin "2") (pinfunction "~{RE}_2") (pintype "input"))
      (node (ref "U3") (pin "3") (pinfunction "DE_3") (pintype "input"))
    )
    (net (code "63") (name "Net-(U1-(MISO)PB6)") (class "Default")
      (node (ref "SPI_PROG") (pin "2") (pinfunction "2_2") (pintype "passive"))
      (node (ref "U1") (pin "7") (pinfunction "(MISO)PB6_7") (pintype "bidirectional"))
    )
    (net (code "64") (name "Net-(U1-(MOSI)PB5)") (class "Default")
      (node (ref "SPI_PROG") (pin "3") (pinfunction "3_3") (pintype "passive"))
      (node (ref "U1") (pin "6") (pinfunction "(MOSI)PB5_6") (pintype "bidirectional"))
    )
    (net (code "65") (name "Net-(U1-(RXD0)PD0)") (class "Default")
      (node (ref "U1") (pin "10") (pinfunction "(RXD0)PD0_10") (pintype "bidirectional"))
      (node (ref "U3") (pin "1") (pinfunction "RO_1") (pintype "output"))
    )
    (net (code "66") (name "Net-(U1-(SCK)PB7)") (class "Default")
      (node (ref "SPI_PROG") (pin "1") (pinfunction "1_1") (pintype "passive"))
      (node (ref "U1") (pin "8") (pinfunction "(SCK)PB7_8") (pintype "bidirectional"))
    )
    (net (code "67") (name "Net-(U1-(TXD0)PD1)") (class "Default")
      (node (ref "U1") (pin "11") (pinfunction "(TXD0)PD1_11") (pintype "bidirectional"))
      (node (ref "U3") (pin "4") (pinfunction "DI_4") (pintype "input"))
    )
    (net (code "68") (name "Net-(U1-RESET)") (class "Default")
      (node (ref "C4") (pin "1") (pinfunction "1_1") (pintype "passive"))
      (node (ref "R1") (pin "2") (pinfunction "2_2") (pintype "passive"))
      (node (ref "RES") (pin "1") (pinfunction "1_1") (pintype "passive"))
      (node (ref "U1") (pin "9") (pinfunction "RESET_9") (pintype "input"))
    )
    (net (code "69") (name "Net-(U1-XTAL1)") (class "Default")
      (node (ref "C2") (pin "1") (pinfunction "1_1") (pintype "passive"))
      (node (ref "Q1") (pin "2") (pinfunction "2_2") (pintype "passive"))
      (node (ref "U1") (pin "19") (pinfunction "XTAL1_19") (pintype "input"))
    )
    (net (code "70") (name "Net-(U1-XTAL2)") (class "Default")
      (node (ref "C1") (pin "1") (pinfunction "1_1") (pintype "passive"))
      (node (ref "Q1") (pin "1") (pinfunction "1_1") (pintype "passive"))
      (node (ref "U1") (pin "18") (pinfunction "XTAL2_18") (pintype "input"))
    )
    (net (code "71") (name "Net-(U3-A)") (class "Default")
      (node (ref "JP3") (pin "1") (pinfunction "1_1") (pintype "passive"))
      (node (ref "R18") (pin "1") (pinfunction "1_1") (pintype "passive"))
      (node (ref "R19") (pin "1") (pinfunction "1_1") (pintype "passive"))
      (node (ref "R22") (pin "1") (pinfunction "1_1") (pintype "passive"))
      (node (ref "U3") (pin "6") (pinfunction "A_6") (pintype "bidirectional"))
    )
    (net (code "72") (name "Net-(U3-B)") (class "Default")
      (node (ref "JP3") (pin "2") (pinfunction "2_2") (pintype "passive"))
      (node (ref "R20") (pin "2") (pinfunction "2_2") (pintype "passive"))
      (node (ref "R21") (pin "2") (pinfunction "2_2") (pintype "passive"))
      (node (ref "R22") (pin "2") (pinfunction "2_2") (pintype "passive"))
      (node (ref "U3") (pin "7") (pinfunction "B_7") (pintype "bidirectional"))
    )
    (net (code "73") (name "unconnected-(DC1-COM-Pad5)") (class "Default")
      (node (ref "DC1") (pin "5") (pinfunction "COM_5") (pintype "passive"))
    )
    (net (code "74") (name "unconnected-(U1-(A9)PC1-Pad22)") (class "Default")
      (node (ref "U1") (pin "22") (pinfunction "(A9)PC1_22") (pintype "bidirectional"))
    )
    (net (code "75") (name "unconnected-(U1-(A10)PC2-Pad23)") (class "Default")
      (node (ref "U1") (pin "23") (pinfunction "(A10)PC2_23") (pintype "bidirectional"))
    )
    (net (code "76") (name "unconnected-(U1-(A11)PC3-Pad24)") (class "Default")
      (node (ref "U1") (pin "24") (pinfunction "(A11)PC3_24") (pintype "bidirectional"))
    )
    (net (code "77") (name "unconnected-(U1-(ALE)PE1-Pad30)") (class "Default")
      (node (ref "U1") (pin "30") (pinfunction "(ALE)PE1_30") (pintype "bidirectional"))
    )
    (net (code "78") (name "unconnected-(U1-(INT2)PE0-Pad31)") (class "Default")
      (node (ref "U1") (pin "31") (pinfunction "(INT2)PE0_31") (pintype "bidirectional"))
    )
    (net (code "79") (name "unconnected-(U1-(OC1B)PE2-Pad29)") (class "Default")
      (node (ref "U1") (pin "29") (pinfunction "(OC1B)PE2_29") (pintype "bidirectional"))
    )
    (net (code "80") (name "unconnected-(U1-(RD)PD7-Pad17)") (class "Default")
      (node (ref "U1") (pin "17") (pinfunction "(RD)PD7_17") (pintype "bidirectional"))
    )
    (net (code "81") (name "unconnected-(U1-(SS)PB4-Pad5)") (class "Default")
      (node (ref "U1") (pin "5") (pinfunction "(SS)PB4_5") (pintype "bidirectional"))
    )
    (net (code "82") (name "unconnected-(U1-(T0)PB0-Pad1)") (class "Default")
      (node (ref "U1") (pin "1") (pinfunction "(T0)PB0_1") (pintype "bidirectional"))
    )
  )
)
